# TFT_MicroSD.net
KiCad netlist of a schematic drawn in Altium Designer
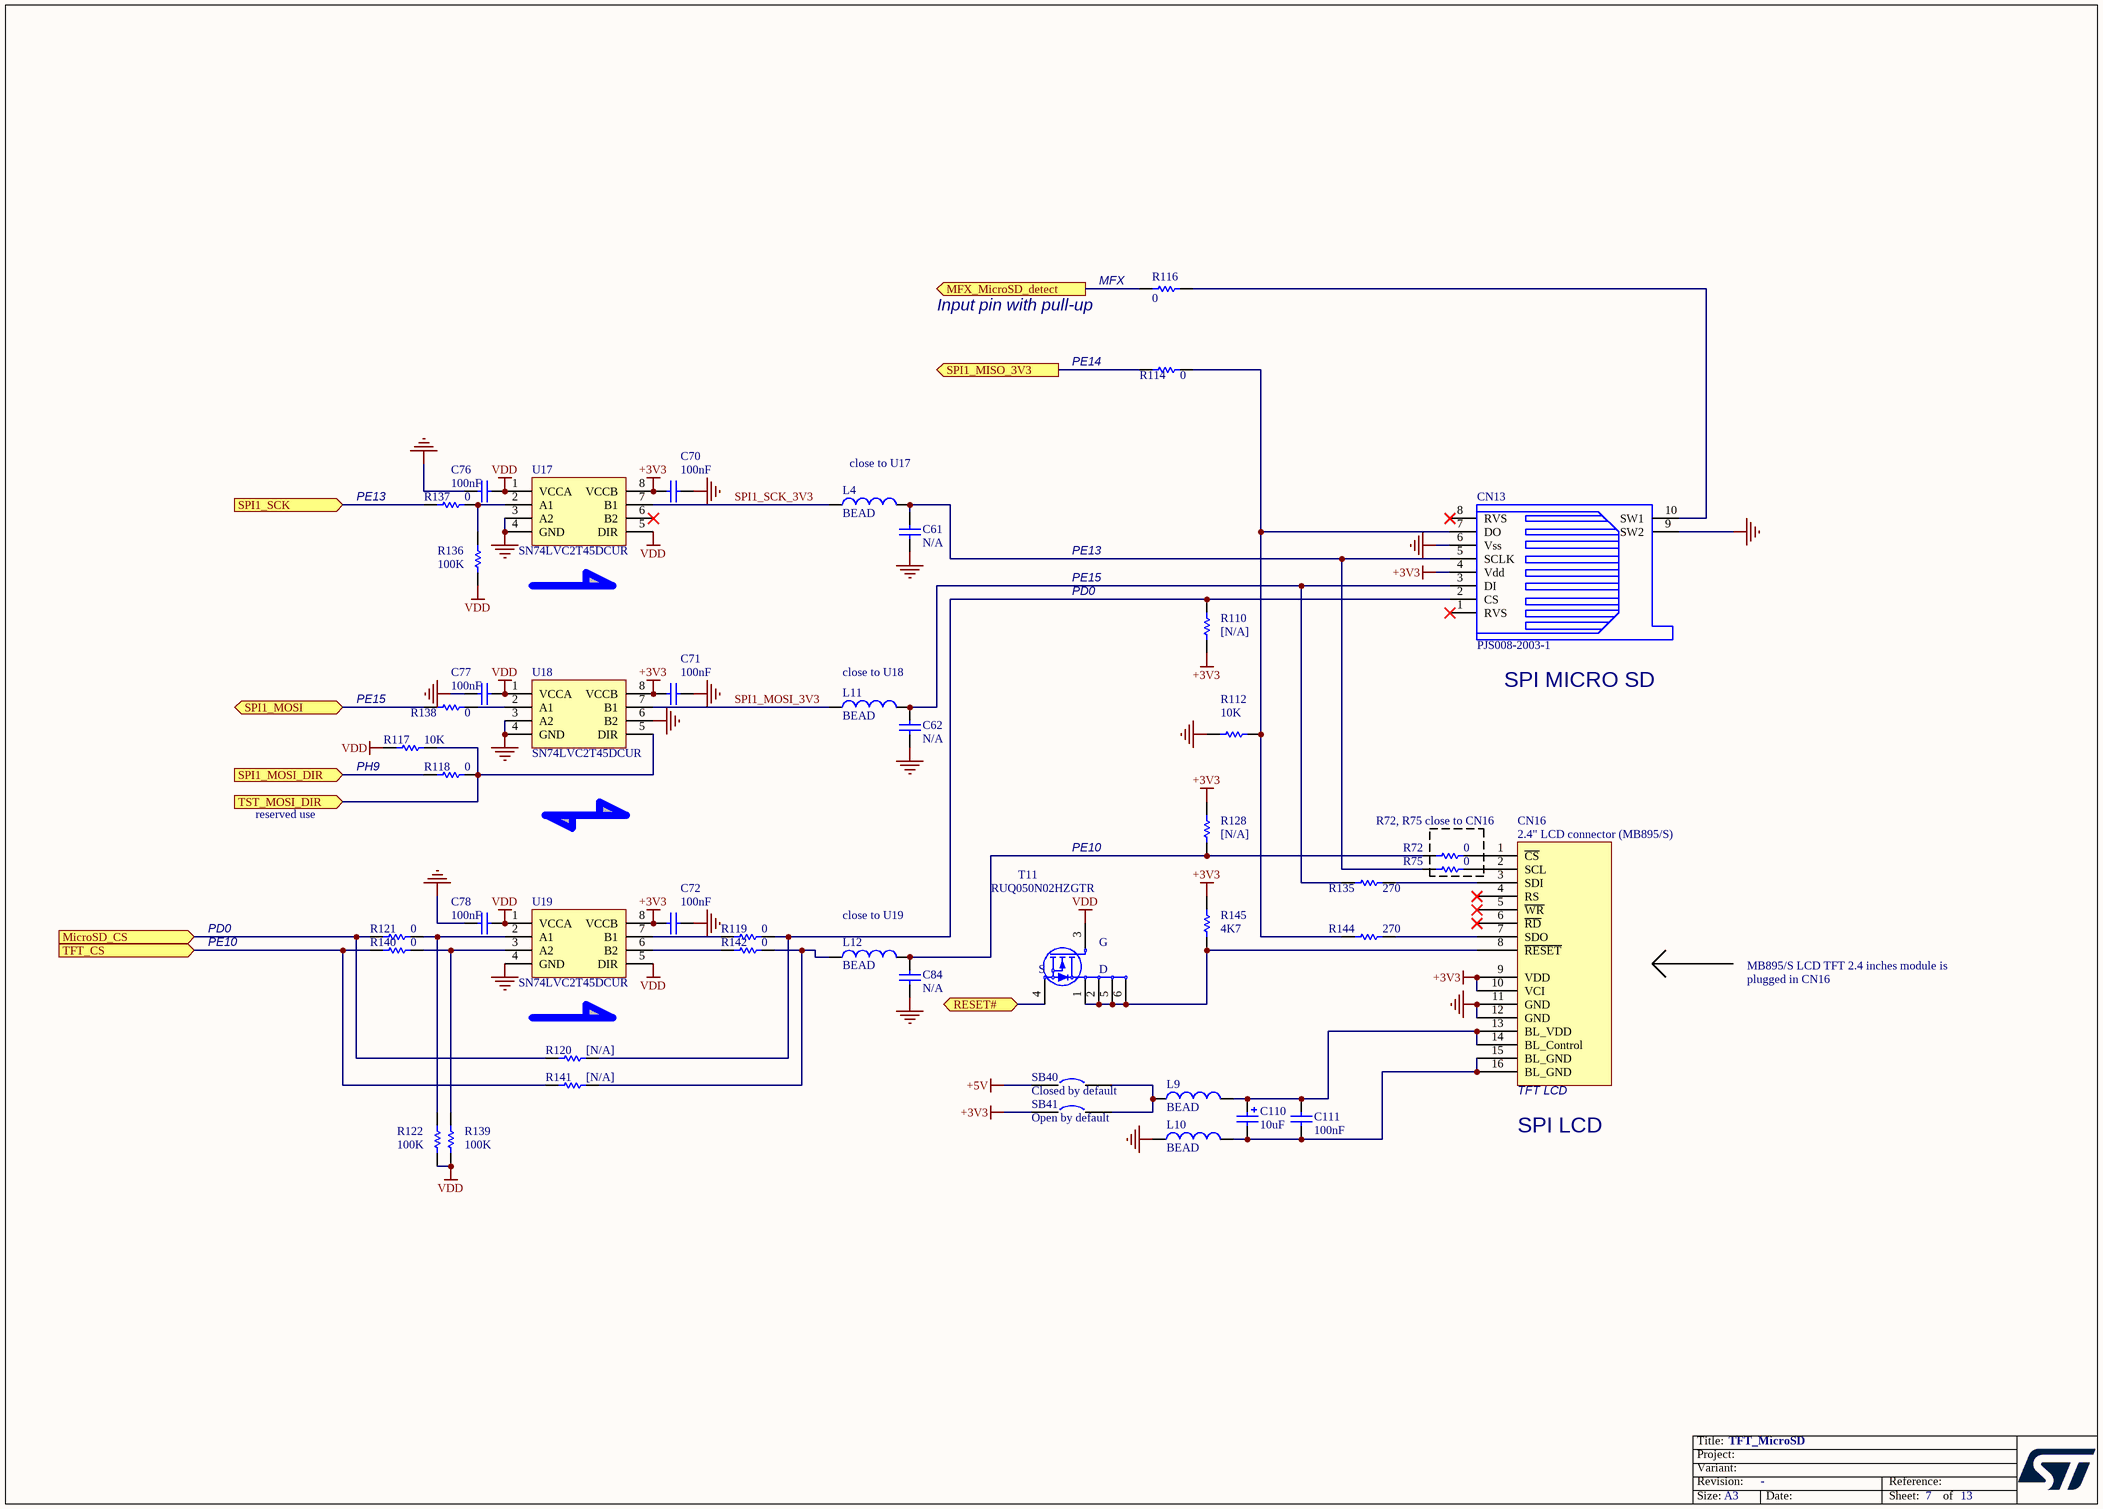
[diagram p0: TFT_MicroSD.SchDoc]

(export (version "E")
  (design (tool "Eeschema 10.0.6"))
  (components
    (comp (ref "C61")
      (value "N/A")
      (footprint "0603C")
      (description "Capacitor")
      (fields (field (name "PUBLISHER") "Altium Limited"))
      (libsource (lib "Miscellaneous Devices") (part "CAP"))
    )
    (comp (ref "C62")
      (value "N/A")
      (footprint "0603C")
      (description "Capacitor")
      (fields (field (name "PUBLISHER") "Altium Limited"))
      (libsource (lib "Miscellaneous Devices") (part "CAP"))
    )
    (comp (ref "C70")
      (value "100nF")
      (footprint "0402C")
      (description "Capacitor")
      (fields (field (name "PUBLISHER") "Altium Limited"))
      (libsource (lib "Miscellaneous Devices") (part "CAP"))
    )
    (comp (ref "C71")
      (value "100nF")
      (footprint "0402C")
      (description "Capacitor")
      (fields (field (name "PUBLISHER") "Altium Limited"))
      (libsource (lib "Miscellaneous Devices") (part "CAP"))
    )
    (comp (ref "C72")
      (value "100nF")
      (footprint "0402C")
      (description "Capacitor")
      (fields (field (name "PUBLISHER") "Altium Limited"))
      (libsource (lib "Miscellaneous Devices") (part "CAP"))
    )
    (comp (ref "C76")
      (value "100nF")
      (footprint "0402C")
      (description "Capacitor")
      (fields (field (name "PUBLISHER") "Altium Limited"))
      (libsource (lib "Miscellaneous Devices") (part "CAP"))
    )
    (comp (ref "C77")
      (value "100nF")
      (footprint "0402C")
      (description "Capacitor")
      (fields (field (name "PUBLISHER") "Altium Limited"))
      (libsource (lib "Miscellaneous Devices") (part "CAP"))
    )
    (comp (ref "C78")
      (value "100nF")
      (footprint "0402C")
      (description "Capacitor")
      (fields (field (name "PUBLISHER") "Altium Limited"))
      (libsource (lib "Miscellaneous Devices") (part "CAP"))
    )
    (comp (ref "C84")
      (value "N/A")
      (footprint "0603C")
      (description "Capacitor")
      (fields (field (name "PUBLISHER") "Altium Limited"))
      (libsource (lib "Miscellaneous Devices") (part "CAP"))
    )
    (comp (ref "C110")
      (value "10uF")
      (footprint "TAN-A")
      (description "Polarized Capacitor (Radial)")
      (fields (field (name "PUBLISHER") "Altium Limited"))
      (libsource (lib "Miscellaneous Devices") (part "Cap Pol1"))
    )
    (comp (ref "C111")
      (value "100nF")
      (footprint "0402C")
      (description "Capacitor")
      (fields (field (name "PUBLISHER") "Altium Limited"))
      (libsource (lib "Miscellaneous Devices") (part "Cap"))
    )
    (comp (ref "CN13")
      (value "PJS008-2003-1")
      (footprint "MSD_PJS008_")
      (libsource (lib "MB1070") (part "SMS016AFA5E"))
    )
    (comp (ref "CN16")
      (value "2.4\" LCD connector (MB895/S)")
      (footprint "MB895CS")
      (libsource (lib "MB1070") (part "ColorLCD_module"))
    )
    (comp (ref "L4")
      (value "BEAD")
      (footprint "0603L")
      (description "Bead,600R,350mA,0603")
      (fields (field (name "PUBLISHER") "Altium Limited"))
      (libsource (lib "Miscellaneous Devices") (part "Inductor"))
    )
    (comp (ref "L9")
      (value "BEAD")
      (footprint "0603L")
      (description "Bead,600R,350mA,0603")
      (fields (field (name "PUBLISHER") "Altium Limited"))
      (libsource (lib "Miscellaneous Devices") (part "Inductor"))
    )
    (comp (ref "L10")
      (value "BEAD")
      (footprint "0603L")
      (description "Bead,600R,350mA,0603")
      (fields (field (name "PUBLISHER") "Altium Limited"))
      (libsource (lib "Miscellaneous Devices") (part "Inductor"))
    )
    (comp (ref "L11")
      (value "BEAD")
      (footprint "0603L")
      (description "Bead,600R,350mA,0603")
      (fields (field (name "PUBLISHER") "Altium Limited"))
      (libsource (lib "Miscellaneous Devices") (part "Inductor"))
    )
    (comp (ref "L12")
      (value "BEAD")
      (footprint "0603L")
      (description "Bead,600R,350mA,0603")
      (fields (field (name "PUBLISHER") "Altium Limited"))
      (libsource (lib "Miscellaneous Devices") (part "Inductor"))
    )
    (comp (ref "R72")
      (value "0")
      (footprint "0603R")
      (description "Resistor")
      (fields (field (name "PUBLISHER") "Altium Limited"))
      (libsource (lib "Miscellaneous Devices") (part "Res1"))
    )
    (comp (ref "R75")
      (value "0")
      (footprint "0603R")
      (description "Resistor")
      (fields (field (name "PUBLISHER") "Altium Limited"))
      (libsource (lib "Miscellaneous Devices") (part "Res1"))
    )
    (comp (ref "R110")
      (value "[N/A]")
      (footprint "0603R")
      (description "Resistor")
      (fields (field (name "PUBLISHER") "Altium Limited"))
      (libsource (lib "Miscellaneous Devices") (part "Res1"))
    )
    (comp (ref "R112")
      (value "10K")
      (footprint "0402R")
      (description "Resistor")
      (fields (field (name "PUBLISHER") "Altium Limited"))
      (libsource (lib "Miscellaneous Devices") (part "Res1"))
    )
    (comp (ref "R114")
      (value "0")
      (footprint "0603R")
      (description "Resistor")
      (fields (field (name "PUBLISHER") "Altium Limited"))
      (libsource (lib "Miscellaneous Devices") (part "Res1"))
    )
    (comp (ref "R116")
      (value "0")
      (footprint "0603R")
      (description "Resistor")
      (fields (field (name "PUBLISHER") "Altium Limited"))
      (libsource (lib "Miscellaneous Devices") (part "Res1"))
    )
    (comp (ref "R117")
      (value "10K")
      (footprint "0402R")
      (description "Resistor")
      (fields (field (name "PUBLISHER") "Altium Limited"))
      (libsource (lib "Miscellaneous Devices") (part "Res1"))
    )
    (comp (ref "R118")
      (value "0")
      (footprint "0603R")
      (description "Resistor")
      (fields (field (name "PUBLISHER") "Altium Limited"))
      (libsource (lib "Miscellaneous Devices") (part "Res1"))
    )
    (comp (ref "R119")
      (value "0")
      (footprint "0603R")
      (description "Resistor")
      (fields (field (name "PUBLISHER") "Altium Limited"))
      (libsource (lib "Miscellaneous Devices") (part "res1"))
    )
    (comp (ref "R120")
      (value "[N/A]")
      (footprint "0603R")
      (description "Resistor")
      (fields (field (name "PUBLISHER") "Altium Limited"))
      (libsource (lib "Miscellaneous Devices") (part "Res1"))
    )
    (comp (ref "R121")
      (value "0")
      (footprint "0603R")
      (description "Resistor")
      (fields (field (name "PUBLISHER") "Altium Limited"))
      (libsource (lib "Miscellaneous Devices") (part "res1"))
    )
    (comp (ref "R122")
      (value "100K")
      (footprint "0603R")
      (description "Resistor")
      (fields (field (name "PUBLISHER") "Altium Limited"))
      (libsource (lib "Miscellaneous Devices") (part "Res1"))
    )
    (comp (ref "R128")
      (value "[N/A]")
      (footprint "0603R")
      (description "Resistor")
      (fields (field (name "PUBLISHER") "Altium Limited"))
      (libsource (lib "Miscellaneous Devices") (part "Res1"))
    )
    (comp (ref "R135")
      (value "270")
      (footprint "0603R")
      (description "Resistor")
      (fields (field (name "PUBLISHER") "Altium Limited"))
      (libsource (lib "Miscellaneous Devices") (part "Res1"))
    )
    (comp (ref "R136")
      (value "100K")
      (footprint "0603R")
      (description "Resistor")
      (fields (field (name "PUBLISHER") "Altium Limited"))
      (libsource (lib "Miscellaneous Devices") (part "Res1"))
    )
    (comp (ref "R137")
      (value "0")
      (footprint "0603R")
      (description "Resistor")
      (fields (field (name "PUBLISHER") "Altium Limited"))
      (libsource (lib "Miscellaneous Devices") (part "res1"))
    )
    (comp (ref "R138")
      (value "0")
      (footprint "0603R")
      (description "Resistor")
      (fields (field (name "PUBLISHER") "Altium Limited"))
      (libsource (lib "Miscellaneous Devices") (part "res1"))
    )
    (comp (ref "R139")
      (value "100K")
      (footprint "0603R")
      (description "Resistor")
      (fields (field (name "PUBLISHER") "Altium Limited"))
      (libsource (lib "Miscellaneous Devices") (part "Res1"))
    )
    (comp (ref "R140")
      (value "0")
      (footprint "0603R")
      (description "Resistor")
      (fields (field (name "PUBLISHER") "Altium Limited"))
      (libsource (lib "Miscellaneous Devices") (part "Res1"))
    )
    (comp (ref "R141")
      (value "[N/A]")
      (footprint "0603R")
      (description "Resistor")
      (fields (field (name "PUBLISHER") "Altium Limited"))
      (libsource (lib "Miscellaneous Devices") (part "Res1"))
    )
    (comp (ref "R142")
      (value "0")
      (footprint "0603R")
      (description "Resistor")
      (fields (field (name "PUBLISHER") "Altium Limited"))
      (libsource (lib "Miscellaneous Devices") (part "res1"))
    )
    (comp (ref "R144")
      (value "270")
      (footprint "0603R")
      (description "Resistor")
      (fields (field (name "PUBLISHER") "Altium Limited"))
      (libsource (lib "Miscellaneous Devices") (part "Res1"))
    )
    (comp (ref "R145")
      (value "4K7")
      (footprint "0402R")
      (description "Resistor")
      (fields (field (name "PUBLISHER") "Altium Limited"))
      (libsource (lib "Miscellaneous Devices") (part "Res1"))
    )
    (comp (ref "SB40")
      (value "Closed by default")
      (footprint "SB_0603")
      (description "Circuit Breaker")
      (fields (field (name "PUBLISHER") "Altium Limited"))
      (libsource (lib "Miscellaneous Devices") (part "Circuit Breaker"))
    )
    (comp (ref "SB41")
      (value "Open by default")
      (footprint "SB_0603")
      (description "Circuit Breaker")
      (fields (field (name "PUBLISHER") "Altium Limited"))
      (libsource (lib "Miscellaneous Devices") (part "Circuit Breaker"))
    )
    (comp (ref "T11")
      (value "RUQ050N02HZGTR")
      (footprint "SOT23-6L")
      (description "STripFETV Power MOSFET, N-CHANNEL 20V - 0.025 - 5A - SOT23-6L")
      (libsource (lib "MCD_TOOLS") (part "STT5N2VH5"))
    )
    (comp (ref "U17")
      (value "SN74LVC2T45DCUR")
      (footprint "USOP8_0R5_2X3R1")
      (libsource (lib "MB818") (part "SN74LVC2T45DCUT"))
    )
    (comp (ref "U18")
      (value "SN74LVC2T45DCUR")
      (footprint "USOP8_0R5_2X3R1")
      (libsource (lib "MB818") (part "SN74LVC2T45DCUT"))
    )
    (comp (ref "U19")
      (value "SN74LVC2T45DCUR")
      (footprint "USOP8_0R5_2X3R1")
      (libsource (lib "MB818") (part "SN74LVC2T45DCUT"))
    )
  )
  (nets
    (net (code "1") (name "+3V3") (class "Default")
      (node (ref "C70") (pin "2") (pinfunction "2_2") (pintype "passive"))
      (node (ref "C71") (pin "2") (pinfunction "2_2") (pintype "passive"))
      (node (ref "C72") (pin "2") (pinfunction "2_2") (pintype "passive"))
      (node (ref "CN13") (pin "4") (pinfunction "Vdd_4") (pintype "passive"))
      (node (ref "CN16") (pin "10") (pinfunction "VCI_10") (pintype "passive"))
      (node (ref "CN16") (pin "9") (pinfunction "VDD_9") (pintype "passive"))
      (node (ref "R110") (pin "2") (pinfunction "2_2") (pintype "passive"))
      (node (ref "R128") (pin "2") (pinfunction "2_2") (pintype "passive"))
      (node (ref "R145") (pin "2") (pinfunction "2_2") (pintype "passive"))
      (node (ref "SB41") (pin "1") (pinfunction "1_1") (pintype "passive"))
      (node (ref "U17") (pin "8") (pinfunction "VCCB_8") (pintype "passive"))
      (node (ref "U18") (pin "8") (pinfunction "VCCB_8") (pintype "passive"))
      (node (ref "U19") (pin "8") (pinfunction "VCCB_8") (pintype "passive"))
    )
    (net (code "2") (name "+5V") (class "Default")
      (node (ref "SB40") (pin "1") (pinfunction "1_1") (pintype "passive"))
    )
    (net (code "3") (name "/MFX_MicroSD_detect") (class "Default")
      (node (ref "R116") (pin "1") (pinfunction "1_1") (pintype "passive"))
    )
    (net (code "4") (name "/MicroSD_CS") (class "Default")
      (node (ref "R120") (pin "1") (pinfunction "1_1") (pintype "passive"))
      (node (ref "R121") (pin "2") (pinfunction "2_2") (pintype "passive"))
    )
    (net (code "5") (name "/RESET#") (class "Default")
      (node (ref "T11") (pin "4") (pinfunction "S_4") (pintype "passive"))
    )
    (net (code "6") (name "/SPI1_MISO_3V3") (class "Default")
      (node (ref "R114") (pin "2") (pinfunction "2_2") (pintype "passive"))
    )
    (net (code "7") (name "/SPI1_MOSI") (class "Default")
      (node (ref "R138") (pin "2") (pinfunction "2_2") (pintype "passive"))
    )
    (net (code "8") (name "/SPI1_MOSI_3V3") (class "Default")
      (node (ref "L11") (pin "1") (pinfunction "1_1") (pintype "passive"))
      (node (ref "U18") (pin "7") (pinfunction "B1_7") (pintype "passive"))
    )
    (net (code "9") (name "/SPI1_MOSI_DIR") (class "Default")
      (node (ref "R118") (pin "2") (pinfunction "2_2") (pintype "passive"))
    )
    (net (code "10") (name "/SPI1_SCK") (class "Default")
      (node (ref "R137") (pin "2") (pinfunction "2_2") (pintype "passive"))
    )
    (net (code "11") (name "/SPI1_SCK_3V3") (class "Default")
      (node (ref "L4") (pin "1") (pinfunction "1_1") (pintype "passive"))
      (node (ref "U17") (pin "7") (pinfunction "B1_7") (pintype "passive"))
    )
    (net (code "12") (name "/TFT_CS") (class "Default")
      (node (ref "R140") (pin "1") (pinfunction "1_1") (pintype "passive"))
      (node (ref "R141") (pin "1") (pinfunction "1_1") (pintype "passive"))
    )
    (net (code "13") (name "/TST_MOSI_DIR") (class "Default")
      (node (ref "R117") (pin "1") (pinfunction "1_1") (pintype "passive"))
      (node (ref "R118") (pin "1") (pinfunction "1_1") (pintype "passive"))
      (node (ref "U18") (pin "5") (pinfunction "DIR_5") (pintype "passive"))
    )
    (net (code "14") (name "GND") (class "Default")
      (node (ref "C61") (pin "1") (pinfunction "1_1") (pintype "passive"))
      (node (ref "C62") (pin "1") (pinfunction "1_1") (pintype "passive"))
      (node (ref "C70") (pin "1") (pinfunction "1_1") (pintype "passive"))
      (node (ref "C71") (pin "1") (pinfunction "1_1") (pintype "passive"))
      (node (ref "C72") (pin "1") (pinfunction "1_1") (pintype "passive"))
      (node (ref "C76") (pin "1") (pinfunction "1_1") (pintype "passive"))
      (node (ref "C77") (pin "1") (pinfunction "1_1") (pintype "passive"))
      (node (ref "C78") (pin "1") (pinfunction "1_1") (pintype "passive"))
      (node (ref "C84") (pin "1") (pinfunction "1_1") (pintype "passive"))
      (node (ref "CN13") (pin "6") (pinfunction "Vss_6") (pintype "passive"))
      (node (ref "CN13") (pin "9") (pinfunction "SW2_9") (pintype "passive"))
      (node (ref "CN16") (pin "11") (pinfunction "GND_11") (pintype "passive"))
      (node (ref "CN16") (pin "12") (pinfunction "GND_12") (pintype "passive"))
      (node (ref "L10") (pin "1") (pinfunction "1_1") (pintype "passive"))
      (node (ref "R112") (pin "1") (pinfunction "1_1") (pintype "passive"))
      (node (ref "U17") (pin "3") (pinfunction "A2_3") (pintype "passive"))
      (node (ref "U17") (pin "4") (pinfunction "GND_4") (pintype "passive"))
      (node (ref "U18") (pin "3") (pinfunction "A2_3") (pintype "passive"))
      (node (ref "U18") (pin "4") (pinfunction "GND_4") (pintype "passive"))
      (node (ref "U18") (pin "6") (pinfunction "B2_6") (pintype "passive"))
      (node (ref "U19") (pin "4") (pinfunction "GND_4") (pintype "passive"))
    )
    (net (code "15") (name "Net-(C84-Pad2)") (class "Default")
      (node (ref "C84") (pin "2") (pinfunction "2_2") (pintype "passive"))
      (node (ref "L12") (pin "2") (pinfunction "2_2") (pintype "passive"))
      (node (ref "R128") (pin "1") (pinfunction "1_1") (pintype "passive"))
      (node (ref "R72") (pin "1") (pinfunction "1_1") (pintype "passive"))
    )
    (net (code "16") (name "Net-(C110-Pad2)") (class "Default")
      (node (ref "C110") (pin "2") (pinfunction "2_2") (pintype "passive"))
      (node (ref "C111") (pin "2") (pinfunction "2_2") (pintype "passive"))
      (node (ref "CN16") (pin "15") (pinfunction "BL_GND_15") (pintype "passive"))
      (node (ref "CN16") (pin "16") (pinfunction "BL_GND_16") (pintype "passive"))
      (node (ref "L10") (pin "2") (pinfunction "2_2") (pintype "passive"))
    )
    (net (code "17") (name "Net-(CN13-CS)") (class "Default")
      (node (ref "CN13") (pin "2") (pinfunction "CS_2") (pintype "passive"))
      (node (ref "R110") (pin "1") (pinfunction "1_1") (pintype "passive"))
      (node (ref "R119") (pin "1") (pinfunction "1_1") (pintype "passive"))
      (node (ref "R120") (pin "2") (pinfunction "2_2") (pintype "passive"))
    )
    (net (code "18") (name "Net-(CN13-DI)") (class "Default")
      (node (ref "C62") (pin "2") (pinfunction "2_2") (pintype "passive"))
      (node (ref "CN13") (pin "3") (pinfunction "DI_3") (pintype "passive"))
      (node (ref "L11") (pin "2") (pinfunction "2_2") (pintype "passive"))
      (node (ref "R135") (pin "2") (pinfunction "2_2") (pintype "passive"))
    )
    (net (code "19") (name "Net-(CN13-DO)") (class "Default")
      (node (ref "CN13") (pin "7") (pinfunction "DO_7") (pintype "passive"))
      (node (ref "R112") (pin "2") (pinfunction "2_2") (pintype "passive"))
      (node (ref "R114") (pin "1") (pinfunction "1_1") (pintype "passive"))
      (node (ref "R144") (pin "1") (pinfunction "1_1") (pintype "passive"))
    )
    (net (code "20") (name "Net-(CN13-SCLK)") (class "Default")
      (node (ref "C61") (pin "2") (pinfunction "2_2") (pintype "passive"))
      (node (ref "CN13") (pin "5") (pinfunction "SCLK_5") (pintype "passive"))
      (node (ref "L4") (pin "2") (pinfunction "2_2") (pintype "passive"))
      (node (ref "R75") (pin "1") (pinfunction "1_1") (pintype "passive"))
    )
    (net (code "21") (name "Net-(CN13-SW1)") (class "Default")
      (node (ref "CN13") (pin "10") (pinfunction "SW1_10") (pintype "passive"))
      (node (ref "R116") (pin "2") (pinfunction "2_2") (pintype "passive"))
    )
    (net (code "22") (name "Net-(CN16-BL_Control)") (class "Default")
      (node (ref "C110") (pin "1") (pinfunction "1_1") (pintype "passive"))
      (node (ref "C111") (pin "1") (pinfunction "1_1") (pintype "passive"))
      (node (ref "CN16") (pin "13") (pinfunction "BL_VDD_13") (pintype "passive"))
      (node (ref "CN16") (pin "14") (pinfunction "BL_Control_14") (pintype "passive"))
      (node (ref "L9") (pin "2") (pinfunction "2_2") (pintype "passive"))
    )
    (net (code "23") (name "Net-(CN16-SCL)") (class "Default")
      (node (ref "CN16") (pin "2") (pinfunction "SCL_2") (pintype "passive"))
      (node (ref "R75") (pin "2") (pinfunction "2_2") (pintype "passive"))
    )
    (net (code "24") (name "Net-(CN16-SDI)") (class "Default")
      (node (ref "CN16") (pin "3") (pinfunction "SDI_3") (pintype "passive"))
      (node (ref "R135") (pin "1") (pinfunction "1_1") (pintype "passive"))
    )
    (net (code "25") (name "Net-(CN16-SDO)") (class "Default")
      (node (ref "CN16") (pin "7") (pinfunction "SDO_7") (pintype "passive"))
      (node (ref "R144") (pin "2") (pinfunction "2_2") (pintype "passive"))
    )
    (net (code "26") (name "Net-(CN16-~{CS})") (class "Default")
      (node (ref "CN16") (pin "1") (pinfunction "~{CS}_1") (pintype "passive"))
      (node (ref "R72") (pin "2") (pinfunction "2_2") (pintype "passive"))
    )
    (net (code "27") (name "Net-(CN16-~{RESET})") (class "Default")
      (node (ref "CN16") (pin "8") (pinfunction "~{RESET}_8") (pintype "passive"))
      (node (ref "R145") (pin "1") (pinfunction "1_1") (pintype "passive"))
      (node (ref "T11") (pin "1") (pinfunction "S_1") (pintype "passive"))
      (node (ref "T11") (pin "2") (pinfunction "S_2") (pintype "passive"))
      (node (ref "T11") (pin "5") (pinfunction "D_5") (pintype "passive"))
      (node (ref "T11") (pin "6") (pinfunction "D_6") (pintype "passive"))
    )
    (net (code "28") (name "Net-(L9-Pad1)") (class "Default")
      (node (ref "L9") (pin "1") (pinfunction "1_1") (pintype "passive"))
      (node (ref "SB40") (pin "2") (pinfunction "2_2") (pintype "passive"))
      (node (ref "SB41") (pin "2") (pinfunction "2_2") (pintype "passive"))
    )
    (net (code "29") (name "Net-(L12-Pad1)") (class "Default")
      (node (ref "L12") (pin "1") (pinfunction "1_1") (pintype "passive"))
      (node (ref "R141") (pin "2") (pinfunction "2_2") (pintype "passive"))
      (node (ref "R142") (pin "1") (pinfunction "1_1") (pintype "passive"))
    )
    (net (code "30") (name "Net-(U17-A1)") (class "Default")
      (node (ref "R136") (pin "1") (pinfunction "1_1") (pintype "passive"))
      (node (ref "R137") (pin "1") (pinfunction "1_1") (pintype "passive"))
      (node (ref "U17") (pin "2") (pinfunction "A1_2") (pintype "passive"))
    )
    (net (code "31") (name "Net-(U18-A1)") (class "Default")
      (node (ref "R138") (pin "1") (pinfunction "1_1") (pintype "passive"))
      (node (ref "U18") (pin "2") (pinfunction "A1_2") (pintype "passive"))
    )
    (net (code "32") (name "Net-(U19-A1)") (class "Default")
      (node (ref "R121") (pin "1") (pinfunction "1_1") (pintype "passive"))
      (node (ref "R122") (pin "1") (pinfunction "1_1") (pintype "passive"))
      (node (ref "U19") (pin "2") (pinfunction "A1_2") (pintype "passive"))
    )
    (net (code "33") (name "Net-(U19-A2)") (class "Default")
      (node (ref "R139") (pin "1") (pinfunction "1_1") (pintype "passive"))
      (node (ref "R140") (pin "2") (pinfunction "2_2") (pintype "passive"))
      (node (ref "U19") (pin "3") (pinfunction "A2_3") (pintype "passive"))
    )
    (net (code "34") (name "Net-(U19-B1)") (class "Default")
      (node (ref "R119") (pin "2") (pinfunction "2_2") (pintype "passive"))
      (node (ref "U19") (pin "7") (pinfunction "B1_7") (pintype "passive"))
    )
    (net (code "35") (name "Net-(U19-B2)") (class "Default")
      (node (ref "R142") (pin "2") (pinfunction "2_2") (pintype "passive"))
      (node (ref "U19") (pin "6") (pinfunction "B2_6") (pintype "passive"))
    )
    (net (code "36") (name "VDD") (class "Default")
      (node (ref "C76") (pin "2") (pinfunction "2_2") (pintype "passive"))
      (node (ref "C77") (pin "2") (pinfunction "2_2") (pintype "passive"))
      (node (ref "C78") (pin "2") (pinfunction "2_2") (pintype "passive"))
      (node (ref "R117") (pin "2") (pinfunction "2_2") (pintype "passive"))
      (node (ref "R122") (pin "2") (pinfunction "2_2") (pintype "passive"))
      (node (ref "R136") (pin "2") (pinfunction "2_2") (pintype "passive"))
      (node (ref "R139") (pin "2") (pinfunction "2_2") (pintype "passive"))
      (node (ref "T11") (pin "3") (pinfunction "G_3") (pintype "passive"))
      (node (ref "U17") (pin "1") (pinfunction "VCCA_1") (pintype "passive"))
      (node (ref "U17") (pin "5") (pinfunction "DIR_5") (pintype "passive"))
      (node (ref "U18") (pin "1") (pinfunction "VCCA_1") (pintype "passive"))
      (node (ref "U19") (pin "1") (pinfunction "VCCA_1") (pintype "passive"))
      (node (ref "U19") (pin "5") (pinfunction "DIR_5") (pintype "passive"))
    )
    (net (code "37") (name "unconnected-(CN13-RVS-Pad1)") (class "Default")
      (node (ref "CN13") (pin "1") (pinfunction "RVS_1") (pintype "passive+no_connect"))
    )
    (net (code "38") (name "unconnected-(CN13-RVS-Pad8)") (class "Default")
      (node (ref "CN13") (pin "8") (pinfunction "RVS_8") (pintype "passive+no_connect"))
    )
    (net (code "39") (name "unconnected-(CN16-RS-Pad4)") (class "Default")
      (node (ref "CN16") (pin "4") (pinfunction "RS_4") (pintype "passive+no_connect"))
    )
    (net (code "40") (name "unconnected-(CN16-~{RD}-Pad6)") (class "Default")
      (node (ref "CN16") (pin "6") (pinfunction "~{RD}_6") (pintype "passive+no_connect"))
    )
    (net (code "41") (name "unconnected-(CN16-~{WR}-Pad5)") (class "Default")
      (node (ref "CN16") (pin "5") (pinfunction "~{WR}_5") (pintype "passive+no_connect"))
    )
    (net (code "42") (name "unconnected-(U17-B2-Pad6)") (class "Default")
      (node (ref "U17") (pin "6") (pinfunction "B2_6") (pintype "passive+no_connect"))
    )
  )
)
